# esp32.net
KiCad netlist of a schematic drawn in Altium Designer
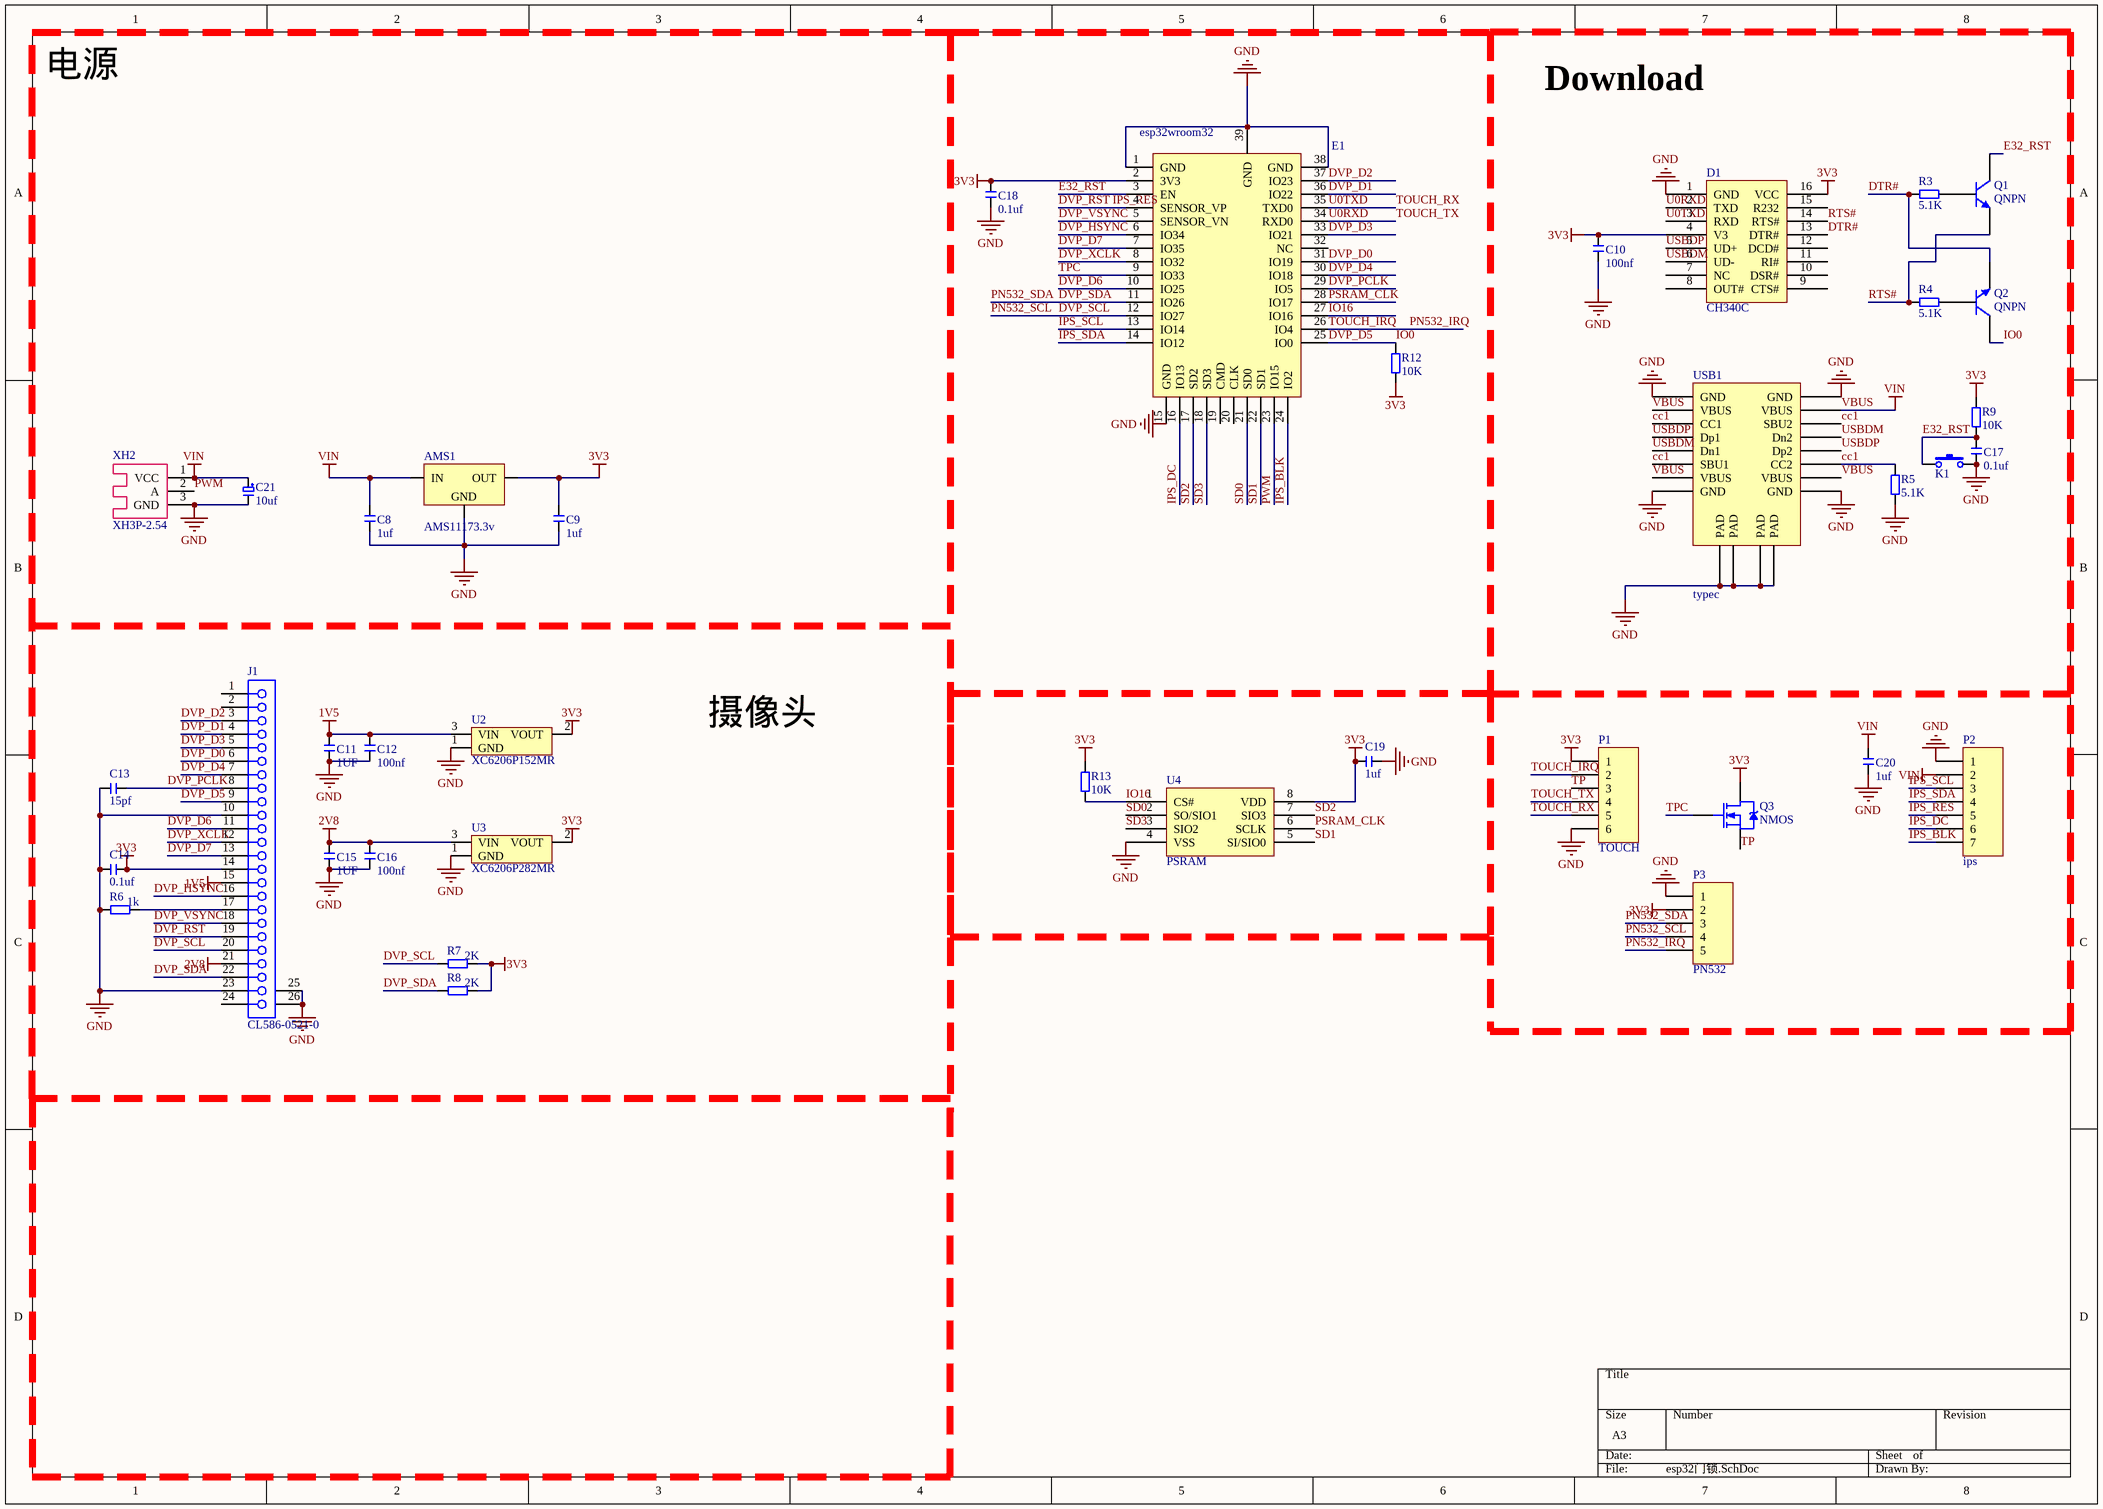
[diagram p0: esp32门锁.SchDoc]

(export (version "E")
  (design (tool "Eeschema 10.0.6"))
  (components
    (comp (ref "AMS1")
      (value "AMS11173.3v")
      (footprint "SOT223")
      (description "Power")
      (libsource (lib "SWJTUCar") (part "AMS1117"))
    )
    (comp (ref "C8")
      (value "1uf")
      (footprint "C0603")
      (description "无极电容")
      (libsource (lib "Robocon_v1.2") (part "CAP"))
    )
    (comp (ref "C9")
      (value "1uf")
      (footprint "C0603")
      (description "无极电容")
      (libsource (lib "Robocon_v1.2") (part "CAP"))
    )
    (comp (ref "C10")
      (value "100nf")
      (footprint "C0603")
      (description "无极电容")
      (libsource (lib "SWJTUCar") (part "CAP"))
    )
    (comp (ref "C11")
      (value "1UF")
      (footprint "C0603")
      (description "无极电容")
      (libsource (lib "SWJTUCar") (part "CAP"))
    )
    (comp (ref "C12")
      (value "100nf")
      (footprint "C0603")
      (description "无极电容")
      (libsource (lib "SWJTUCar") (part "CAP"))
    )
    (comp (ref "C13")
      (value "15pf")
      (footprint "C0603")
      (description "无极电容")
      (libsource (lib "SWJTUCar") (part "CAP"))
    )
    (comp (ref "C14")
      (value "0.1uf")
      (footprint "C0603")
      (description "无极电容")
      (libsource (lib "SWJTUCar") (part "CAP"))
    )
    (comp (ref "C15")
      (value "1UF")
      (footprint "C0603")
      (description "无极电容")
      (libsource (lib "SWJTUCar") (part "CAP"))
    )
    (comp (ref "C16")
      (value "100nf")
      (footprint "C0603")
      (description "无极电容")
      (libsource (lib "SWJTUCar") (part "CAP"))
    )
    (comp (ref "C17")
      (value "0.1uf")
      (footprint "C0603")
      (description "无极电容")
      (libsource (lib "SWJTUCar") (part "CAP"))
    )
    (comp (ref "C18")
      (value "0.1uf")
      (footprint "C0603")
      (description "无极电容")
      (libsource (lib "SWJTUCar") (part "CAP"))
    )
    (comp (ref "C19")
      (value "1uf")
      (footprint "C0603")
      (description "无极电容")
      (libsource (lib "SWJTUCar") (part "CAP"))
    )
    (comp (ref "C20")
      (value "1uf")
      (footprint "C0603")
      (description "无极电容")
      (libsource (lib "SWJTUCar") (part "CAP"))
    )
    (comp (ref "C21")
      (value "10uf")
      (footprint "C4X4")
      (description "电解电容")
      (libsource (lib "SWJTUCar") (part "CAP-Pole_1"))
    )
    (comp (ref "D1") (value "CH340C") (footprint "CH340C") (libsource (lib "LHM_LIB") (part "ch340c")))
    (comp (ref "E1") (value "esp32wroom32") (footprint "esp32U") (libsource (lib "LHM_LIB") (part "esp32")))
    (comp (ref "J1")
      (value "CL586-0521-0")
      (footprint "FH12-24S-0.5SH")
      (description "FH12 Series, \"Flip-Lock\" SMT/ZIF Connector - 0.5mm Spaced Bottom Contact")
      (fields (field (name "PUBLISHER") "Altium Limited"))
      (libsource (lib "HRS FPC-FFC FH12 Series") (part "CL586-0521-0"))
    )
    (comp (ref "K1")
      (value "Key-PB")
      (footprint "KEY-SMD1")
      (description "轻触开关")
      (libsource (lib "SWJTUCar") (part "Key-PB"))
    )
    (comp (ref "P1")
      (value "TOUCH")
      (footprint "HDR1X6")
      (description "Header, 6-Pin")
      (fields (field (name "PUBLISHER") "Altium Limited"))
      (libsource (lib "Miscellaneous Connectors") (part "Header 6"))
    )
    (comp (ref "P2")
      (value "ips")
      (footprint "HDR1X7")
      (description "Header, 7-Pin")
      (fields (field (name "PUBLISHER") "Altium Limited"))
      (libsource (lib "Miscellaneous Connectors") (part "Header 7"))
    )
    (comp (ref "P3")
      (value "PN532")
      (footprint "HDR1X5")
      (description "Header, 5-Pin")
      (fields (field (name "PUBLISHER") "Altium Limited"))
      (libsource (lib "Miscellaneous Connectors") (part "Header 5"))
    )
    (comp (ref "Q1")
      (value "QNPN")
      (footprint "SOT-23B_N")
      (description "NPN Bipolar Transistor")
      (fields (field (name "PUBLISHER") "Altium Limited"))
      (libsource (lib "Miscellaneous Devices") (part "QNPN"))
    )
    (comp (ref "Q2")
      (value "QNPN")
      (footprint "SOT-23B_N")
      (description "NPN Bipolar Transistor")
      (fields (field (name "PUBLISHER") "Altium Limited"))
      (libsource (lib "Miscellaneous Devices") (part "QNPN"))
    )
    (comp (ref "Q3")
      (value "NMOS")
      (footprint "SOT23")
      (description "HEXFET Power MOSFET")
      (fields (field (name "PUBLISHER") "Altium Limited"))
      (libsource (lib "Robocon_v1.2") (part "NOMS"))
    )
    (comp (ref "R3")
      (value "5.1K")
      (footprint "R0603")
      (description "电阻")
      (libsource (lib "SWJTUCar") (part "RES"))
    )
    (comp (ref "R4")
      (value "5.1K")
      (footprint "R0603")
      (description "电阻")
      (libsource (lib "SWJTUCar") (part "RES"))
    )
    (comp (ref "R5")
      (value "5.1K")
      (footprint "R0603")
      (description "电阻")
      (libsource (lib "SWJTUCar") (part "RES"))
    )
    (comp (ref "R6")
      (value "1k")
      (footprint "R0603")
      (description "电阻")
      (libsource (lib "SWJTUCar") (part "RES"))
    )
    (comp (ref "R7")
      (value "2K")
      (footprint "R0603")
      (description "电阻")
      (libsource (lib "SWJTUCar") (part "RES"))
    )
    (comp (ref "R8")
      (value "2K")
      (footprint "R0603")
      (description "电阻")
      (libsource (lib "SWJTUCar") (part "RES"))
    )
    (comp (ref "R9")
      (value "10K")
      (footprint "R0603")
      (description "电阻")
      (libsource (lib "SWJTUCar") (part "RES"))
    )
    (comp (ref "R12")
      (value "10K")
      (footprint "R0603")
      (description "电阻")
      (libsource (lib "SWJTUCar") (part "RES"))
    )
    (comp (ref "R13")
      (value "10K")
      (footprint "R0603")
      (description "电阻")
      (libsource (lib "SWJTUCar") (part "RES"))
    )
    (comp (ref "U2")
      (value "XC6206P152MR")
      (footprint "SOT23-3")
      (description "LDO,SOT23,1.2~5.0V")
      (libsource (lib "Win_Lib") (part "XC6206"))
    )
    (comp (ref "U3")
      (value "XC6206P282MR")
      (footprint "SOT23-3")
      (description "LDO,SOT23,1.2~5.0V")
      (libsource (lib "Win_Lib") (part "XC6206"))
    )
    (comp (ref "U4") (value "PSRAM") (footprint "PSRAM") (libsource (lib "LHM_LIB") (part "PSRAM")))
    (comp (ref "USB1")
      (value "typec")
      (footprint "USB-C-SMD_TYPE-C16PIN")
      (libsource (lib "LHM_LIB") (part "typec16p四脚插板"))
    )
    (comp (ref "XH2")
      (value "XH3P-2.54")
      (footprint "XH2.54-3")
      (description "XH2.54小白头")
      (libsource (lib "SWJTUCar") (part "XH3P-2.54"))
    )
  )
  (nets
    (net (code "1") (name "/DTR#") (class "Default")
      (node (ref "D1") (pin "13") (pinfunction "DTR#_13") (pintype "passive"))
      (node (ref "Q2") (pin "3") (pinfunction "E_3") (pintype "passive"))
      (node (ref "R3") (pin "2") (pinfunction "2_2") (pintype "passive"))
    )
    (net (code "2") (name "/DVP_D0") (class "Default")
      (node (ref "E1") (pin "31") (pinfunction "IO19_31") (pintype "passive"))
      (node (ref "J1") (pin "6") (pinfunction "6_6") (pintype "passive"))
    )
    (net (code "3") (name "/DVP_D1") (class "Default")
      (node (ref "E1") (pin "36") (pinfunction "IO22_36") (pintype "passive"))
      (node (ref "J1") (pin "4") (pinfunction "4_4") (pintype "passive"))
    )
    (net (code "4") (name "/DVP_D2") (class "Default")
      (node (ref "E1") (pin "37") (pinfunction "IO23_37") (pintype "passive"))
      (node (ref "J1") (pin "3") (pinfunction "3_3") (pintype "passive"))
    )
    (net (code "5") (name "/DVP_D3") (class "Default")
      (node (ref "E1") (pin "33") (pinfunction "IO21_33") (pintype "passive"))
      (node (ref "J1") (pin "5") (pinfunction "5_5") (pintype "passive"))
    )
    (net (code "6") (name "/DVP_D4") (class "Default")
      (node (ref "E1") (pin "30") (pinfunction "IO18_30") (pintype "passive"))
      (node (ref "J1") (pin "7") (pinfunction "7_7") (pintype "passive"))
    )
    (net (code "7") (name "/DVP_D5") (class "Default")
      (node (ref "E1") (pin "25") (pinfunction "IO0_25") (pintype "passive"))
      (node (ref "J1") (pin "9") (pinfunction "9_9") (pintype "passive"))
      (node (ref "Q2") (pin "1") (pinfunction "C_1") (pintype "passive"))
      (node (ref "R12") (pin "1") (pinfunction "1_1") (pintype "passive"))
    )
    (net (code "8") (name "/DVP_D6") (class "Default")
      (node (ref "E1") (pin "10") (pinfunction "IO25_10") (pintype "passive"))
      (node (ref "J1") (pin "11") (pinfunction "11_11") (pintype "passive"))
    )
    (net (code "9") (name "/DVP_D7") (class "Default")
      (node (ref "E1") (pin "7") (pinfunction "IO35_7") (pintype "passive"))
      (node (ref "J1") (pin "13") (pinfunction "13_13") (pintype "passive"))
    )
    (net (code "10") (name "/DVP_HSYNC") (class "Default")
      (node (ref "E1") (pin "6") (pinfunction "IO34_6") (pintype "passive"))
      (node (ref "J1") (pin "16") (pinfunction "16_16") (pintype "passive"))
    )
    (net (code "11") (name "/DVP_PCLK") (class "Default")
      (node (ref "C13") (pin "1") (pinfunction "1_1") (pintype "passive"))
      (node (ref "E1") (pin "29") (pinfunction "IO5_29") (pintype "passive"))
      (node (ref "J1") (pin "8") (pinfunction "8_8") (pintype "passive"))
    )
    (net (code "12") (name "/DVP_RST") (class "Default")
      (node (ref "E1") (pin "4") (pinfunction "SENSOR_VP_4") (pintype "passive"))
      (node (ref "J1") (pin "19") (pinfunction "19_19") (pintype "passive"))
      (node (ref "P2") (pin "5") (pinfunction "5_5") (pintype "passive"))
    )
    (net (code "13") (name "/DVP_SCL") (class "Default")
      (node (ref "E1") (pin "12") (pinfunction "IO27_12") (pintype "passive"))
      (node (ref "J1") (pin "20") (pinfunction "20_20") (pintype "passive"))
      (node (ref "P3") (pin "4") (pinfunction "4_4") (pintype "passive"))
      (node (ref "R7") (pin "2") (pinfunction "2_2") (pintype "passive"))
    )
    (net (code "14") (name "/DVP_SDA") (class "Default")
      (node (ref "E1") (pin "11") (pinfunction "IO26_11") (pintype "passive"))
      (node (ref "J1") (pin "22") (pinfunction "22_22") (pintype "passive"))
      (node (ref "P3") (pin "3") (pinfunction "3_3") (pintype "passive"))
      (node (ref "R8") (pin "2") (pinfunction "2_2") (pintype "passive"))
    )
    (net (code "15") (name "/DVP_VSYNC") (class "Default")
      (node (ref "E1") (pin "5") (pinfunction "SENSOR_VN_5") (pintype "passive"))
      (node (ref "J1") (pin "18") (pinfunction "18_18") (pintype "passive"))
    )
    (net (code "16") (name "/DVP_XCLK") (class "Default")
      (node (ref "E1") (pin "8") (pinfunction "IO32_8") (pintype "passive"))
      (node (ref "J1") (pin "12") (pinfunction "12_12") (pintype "passive"))
    )
    (net (code "17") (name "/E32_RST") (class "Default")
      (node (ref "C17") (pin "2") (pinfunction "2_2") (pintype "passive"))
      (node (ref "E1") (pin "3") (pinfunction "EN_3") (pintype "passive"))
      (node (ref "K1") (pin "1") (pinfunction "1_1") (pintype "passive"))
      (node (ref "Q1") (pin "1") (pinfunction "C_1") (pintype "passive"))
      (node (ref "R9") (pin "1") (pinfunction "1_1") (pintype "passive"))
    )
    (net (code "18") (name "/IO16") (class "Default")
      (node (ref "E1") (pin "27") (pinfunction "IO16_27") (pintype "passive"))
      (node (ref "R13") (pin "2") (pinfunction "2_2") (pintype "passive"))
      (node (ref "U4") (pin "1") (pinfunction "CS#_1") (pintype "passive"))
    )
    (net (code "19") (name "/IPS_BLK") (class "Default")
      (node (ref "E1") (pin "24") (pinfunction "IO2_24") (pintype "passive"))
      (node (ref "P2") (pin "7") (pinfunction "7_7") (pintype "passive"))
    )
    (net (code "20") (name "/IPS_DC") (class "Default")
      (node (ref "E1") (pin "16") (pinfunction "IO13_16") (pintype "passive"))
      (node (ref "P2") (pin "6") (pinfunction "6_6") (pintype "passive"))
    )
    (net (code "21") (name "/IPS_SCL") (class "Default")
      (node (ref "E1") (pin "13") (pinfunction "IO14_13") (pintype "passive"))
      (node (ref "P2") (pin "3") (pinfunction "3_3") (pintype "passive"))
    )
    (net (code "22") (name "/IPS_SDA") (class "Default")
      (node (ref "E1") (pin "14") (pinfunction "IO12_14") (pintype "passive"))
      (node (ref "P2") (pin "4") (pinfunction "4_4") (pintype "passive"))
    )
    (net (code "23") (name "/PN532_IRQ") (class "Default")
      (node (ref "E1") (pin "26") (pinfunction "IO4_26") (pintype "passive"))
      (node (ref "P1") (pin "2") (pinfunction "2_2") (pintype "passive"))
      (node (ref "P3") (pin "5") (pinfunction "5_5") (pintype "passive"))
    )
    (net (code "24") (name "/PSRAM_CLK") (class "Default")
      (node (ref "E1") (pin "28") (pinfunction "IO17_28") (pintype "passive"))
      (node (ref "U4") (pin "6") (pinfunction "SCLK_6") (pintype "passive"))
    )
    (net (code "25") (name "/PWM") (class "Default")
      (node (ref "E1") (pin "23") (pinfunction "IO15_23") (pintype "passive"))
      (node (ref "XH2") (pin "2") (pinfunction "A_2") (pintype "passive"))
    )
    (net (code "26") (name "/RTS#") (class "Default")
      (node (ref "D1") (pin "14") (pinfunction "RTS#_14") (pintype "passive"))
      (node (ref "Q1") (pin "3") (pinfunction "E_3") (pintype "passive"))
      (node (ref "R4") (pin "2") (pinfunction "2_2") (pintype "passive"))
    )
    (net (code "27") (name "/SD0") (class "Default")
      (node (ref "E1") (pin "21") (pinfunction "SD0_21") (pintype "passive"))
      (node (ref "U4") (pin "2") (pinfunction "SO/SIO1_2") (pintype "passive"))
    )
    (net (code "28") (name "/SD1") (class "Default")
      (node (ref "E1") (pin "22") (pinfunction "SD1_22") (pintype "passive"))
      (node (ref "U4") (pin "5") (pinfunction "SI/SIO0_5") (pintype "passive"))
    )
    (net (code "29") (name "/SD2") (class "Default")
      (node (ref "E1") (pin "17") (pinfunction "SD2_17") (pintype "passive"))
      (node (ref "U4") (pin "7") (pinfunction "SIO3_7") (pintype "passive"))
    )
    (net (code "30") (name "/SD3") (class "Default")
      (node (ref "E1") (pin "18") (pinfunction "SD3_18") (pintype "passive"))
      (node (ref "U4") (pin "3") (pinfunction "SIO2_3") (pintype "passive"))
    )
    (net (code "31") (name "/TOUCH_RX") (class "Default")
      (node (ref "D1") (pin "3") (pinfunction "RXD_3") (pintype "passive"))
      (node (ref "E1") (pin "35") (pinfunction "TXD0_35") (pintype "passive"))
      (node (ref "P1") (pin "5") (pinfunction "5_5") (pintype "passive"))
    )
    (net (code "32") (name "/TOUCH_TX") (class "Default")
      (node (ref "D1") (pin "2") (pinfunction "TXD_2") (pintype "passive"))
      (node (ref "E1") (pin "34") (pinfunction "RXD0_34") (pintype "passive"))
      (node (ref "P1") (pin "4") (pinfunction "4_4") (pintype "passive"))
    )
    (net (code "33") (name "/TP") (class "Default")
      (node (ref "P1") (pin "3") (pinfunction "3_3") (pintype "passive"))
      (node (ref "Q3") (pin "3") (pinfunction "S_3") (pintype "passive"))
    )
    (net (code "34") (name "/TPC") (class "Default")
      (node (ref "E1") (pin "9") (pinfunction "IO33_9") (pintype "passive"))
      (node (ref "Q3") (pin "1") (pinfunction "15_1") (pintype "passive"))
    )
    (net (code "35") (name "/USBDM") (class "Default")
      (node (ref "D1") (pin "6") (pinfunction "UD-_6") (pintype "passive"))
      (node (ref "USB1") (pin "A7") (pinfunction "Dn1_A7") (pintype "passive"))
      (node (ref "USB1") (pin "B7") (pinfunction "Dn2_B7") (pintype "passive"))
    )
    (net (code "36") (name "/USBDP") (class "Default")
      (node (ref "D1") (pin "5") (pinfunction "UD+_5") (pintype "passive"))
      (node (ref "USB1") (pin "A6") (pinfunction "Dp1_A6") (pintype "passive"))
      (node (ref "USB1") (pin "B6") (pinfunction "Dp2_B6") (pintype "passive"))
    )
    (net (code "37") (name "/cc1") (class "Default")
      (node (ref "R5") (pin "2") (pinfunction "2_2") (pintype "passive"))
      (node (ref "USB1") (pin "A5") (pinfunction "CC1_A5") (pintype "passive"))
      (node (ref "USB1") (pin "A8") (pinfunction "SBU1_A8") (pintype "passive"))
      (node (ref "USB1") (pin "B5") (pinfunction "CC2_B5") (pintype "passive"))
      (node (ref "USB1") (pin "B8") (pinfunction "SBU2_B8") (pintype "passive"))
    )
    (net (code "38") (name "1V5") (class "Default")
      (node (ref "C11") (pin "2") (pinfunction "2_2") (pintype "passive"))
      (node (ref "C12") (pin "2") (pinfunction "2_2") (pintype "passive"))
      (node (ref "J1") (pin "15") (pinfunction "15_15") (pintype "passive"))
      (node (ref "U2") (pin "3") (pinfunction "VIN_3") (pintype "passive"))
    )
    (net (code "39") (name "2V8") (class "Default")
      (node (ref "C15") (pin "2") (pinfunction "2_2") (pintype "passive"))
      (node (ref "C16") (pin "2") (pinfunction "2_2") (pintype "passive"))
      (node (ref "J1") (pin "21") (pinfunction "21_21") (pintype "passive"))
      (node (ref "U3") (pin "3") (pinfunction "VIN_3") (pintype "passive"))
    )
    (net (code "40") (name "3V3") (class "Default")
      (node (ref "AMS1") (pin "2") (pinfunction "OUT_2") (pintype "power_in"))
      (node (ref "C10") (pin "2") (pinfunction "2_2") (pintype "passive"))
      (node (ref "C14") (pin "1") (pinfunction "1_1") (pintype "passive"))
      (node (ref "C18") (pin "2") (pinfunction "2_2") (pintype "passive"))
      (node (ref "C19") (pin "2") (pinfunction "2_2") (pintype "passive"))
      (node (ref "C9") (pin "2") (pinfunction "2_2") (pintype "passive"))
      (node (ref "D1") (pin "16") (pinfunction "VCC_16") (pintype "passive"))
      (node (ref "D1") (pin "4") (pinfunction "V3_4") (pintype "passive"))
      (node (ref "E1") (pin "2") (pinfunction "3V3_2") (pintype "passive"))
      (node (ref "J1") (pin "14") (pinfunction "14_14") (pintype "passive"))
      (node (ref "P1") (pin "1") (pinfunction "1_1") (pintype "passive"))
      (node (ref "P3") (pin "2") (pinfunction "2_2") (pintype "passive"))
      (node (ref "Q3") (pin "2") (pinfunction "D_2") (pintype "passive"))
      (node (ref "R12") (pin "2") (pinfunction "2_2") (pintype "passive"))
      (node (ref "R13") (pin "1") (pinfunction "1_1") (pintype "passive"))
      (node (ref "R7") (pin "1") (pinfunction "1_1") (pintype "passive"))
      (node (ref "R8") (pin "1") (pinfunction "1_1") (pintype "passive"))
      (node (ref "R9") (pin "2") (pinfunction "2_2") (pintype "passive"))
      (node (ref "U2") (pin "2") (pinfunction "VOUT_2") (pintype "passive"))
      (node (ref "U3") (pin "2") (pinfunction "VOUT_2") (pintype "passive"))
      (node (ref "U4") (pin "8") (pinfunction "VDD_8") (pintype "passive"))
    )
    (net (code "41") (name "GND") (class "Default")
      (node (ref "AMS1") (pin "1") (pinfunction "GND_1") (pintype "power_in"))
      (node (ref "C10") (pin "1") (pinfunction "1_1") (pintype "passive"))
      (node (ref "C11") (pin "1") (pinfunction "1_1") (pintype "passive"))
      (node (ref "C12") (pin "1") (pinfunction "1_1") (pintype "passive"))
      (node (ref "C13") (pin "2") (pinfunction "2_2") (pintype "passive"))
      (node (ref "C14") (pin "2") (pinfunction "2_2") (pintype "passive"))
      (node (ref "C15") (pin "1") (pinfunction "1_1") (pintype "passive"))
      (node (ref "C16") (pin "1") (pinfunction "1_1") (pintype "passive"))
      (node (ref "C17") (pin "1") (pinfunction "1_1") (pintype "passive"))
      (node (ref "C18") (pin "1") (pinfunction "1_1") (pintype "passive"))
      (node (ref "C19") (pin "1") (pinfunction "1_1") (pintype "passive"))
      (node (ref "C20") (pin "2") (pinfunction "2_2") (pintype "passive"))
      (node (ref "C21") (pin "2") (pinfunction "2_2") (pintype "passive"))
      (node (ref "C8") (pin "1") (pinfunction "1_1") (pintype "passive"))
      (node (ref "C9") (pin "1") (pinfunction "1_1") (pintype "passive"))
      (node (ref "D1") (pin "1") (pinfunction "GND_1") (pintype "passive"))
      (node (ref "E1") (pin "1") (pinfunction "GND_1") (pintype "passive"))
      (node (ref "E1") (pin "15") (pinfunction "GND_15") (pintype "passive"))
      (node (ref "E1") (pin "38") (pinfunction "GND_38") (pintype "passive"))
      (node (ref "E1") (pin "39") (pinfunction "GND_39") (pintype "passive"))
      (node (ref "J1") (pin "10") (pinfunction "10_10") (pintype "passive"))
      (node (ref "J1") (pin "23") (pinfunction "23_23") (pintype "passive"))
      (node (ref "J1") (pin "25") (pinfunction "MH1_25") (pintype "passive"))
      (node (ref "J1") (pin "26") (pinfunction "MH2_26") (pintype "passive"))
      (node (ref "K1") (pin "2") (pinfunction "2_2") (pintype "passive"))
      (node (ref "P1") (pin "6") (pinfunction "6_6") (pintype "passive"))
      (node (ref "P2") (pin "1") (pinfunction "1_1") (pintype "passive"))
      (node (ref "P3") (pin "1") (pinfunction "1_1") (pintype "passive"))
      (node (ref "R5") (pin "1") (pinfunction "1_1") (pintype "passive"))
      (node (ref "R6") (pin "2") (pinfunction "2_2") (pintype "passive"))
      (node (ref "U2") (pin "1") (pinfunction "GND_1") (pintype "passive"))
      (node (ref "U3") (pin "1") (pinfunction "GND_1") (pintype "passive"))
      (node (ref "U4") (pin "4") (pinfunction "VSS_4") (pintype "passive"))
      (node (ref "USB1") (pin "A1B12") (pinfunction "GND_A1B12") (pintype "passive"))
      (node (ref "USB1") (pin "B1A12") (pinfunction "GND_B1A12") (pintype "passive"))
      (node (ref "USB1") (pin "S") (pinfunction "PAD_S") (pintype "passive"))
      (node (ref "XH2") (pin "3") (pinfunction "GND_3") (pintype "passive"))
    )
    (net (code "42") (name "Net-(J1-Pad17)") (class "Default")
      (node (ref "J1") (pin "17") (pinfunction "17_17") (pintype "passive"))
      (node (ref "R6") (pin "1") (pinfunction "1_1") (pintype "passive"))
    )
    (net (code "43") (name "Net-(Q1-B)") (class "Default")
      (node (ref "Q1") (pin "2") (pinfunction "B_2") (pintype "passive"))
      (node (ref "R3") (pin "1") (pinfunction "1_1") (pintype "passive"))
    )
    (net (code "44") (name "Net-(Q2-B)") (class "Default")
      (node (ref "Q2") (pin "2") (pinfunction "B_2") (pintype "passive"))
      (node (ref "R4") (pin "1") (pinfunction "1_1") (pintype "passive"))
    )
    (net (code "45") (name "VIN") (class "Default")
      (node (ref "AMS1") (pin "3") (pinfunction "IN_3") (pintype "power_in"))
      (node (ref "C20") (pin "1") (pinfunction "1_1") (pintype "passive"))
      (node (ref "C21") (pin "1") (pinfunction "1_1") (pintype "passive"))
      (node (ref "C8") (pin "2") (pinfunction "2_2") (pintype "passive"))
      (node (ref "P2") (pin "2") (pinfunction "2_2") (pintype "passive"))
      (node (ref "USB1") (pin "A4B9") (pinfunction "VBUS_A4B9") (pintype "passive"))
      (node (ref "USB1") (pin "B4A9") (pinfunction "VBUS_B4A9") (pintype "passive"))
      (node (ref "XH2") (pin "1") (pinfunction "VCC_1") (pintype "passive"))
    )
    (net (code "46") (name "unconnected-(D1-CTS#-Pad9)") (class "Default")
      (node (ref "D1") (pin "9") (pinfunction "CTS#_9") (pintype "passive"))
    )
    (net (code "47") (name "unconnected-(D1-DCD#-Pad12)") (class "Default")
      (node (ref "D1") (pin "12") (pinfunction "DCD#_12") (pintype "passive"))
    )
    (net (code "48") (name "unconnected-(D1-DSR#-Pad10)") (class "Default")
      (node (ref "D1") (pin "10") (pinfunction "DSR#_10") (pintype "passive"))
    )
    (net (code "49") (name "unconnected-(D1-NC-Pad7)") (class "Default")
      (node (ref "D1") (pin "7") (pinfunction "NC_7") (pintype "passive"))
    )
    (net (code "50") (name "unconnected-(D1-OUT#-Pad8)") (class "Default")
      (node (ref "D1") (pin "8") (pinfunction "OUT#_8") (pintype "passive"))
    )
    (net (code "51") (name "unconnected-(D1-R232-Pad15)") (class "Default")
      (node (ref "D1") (pin "15") (pinfunction "R232_15") (pintype "passive"))
    )
    (net (code "52") (name "unconnected-(D1-RI#-Pad11)") (class "Default")
      (node (ref "D1") (pin "11") (pinfunction "RI#_11") (pintype "passive"))
    )
    (net (code "53") (name "unconnected-(E1-CLK-Pad20)") (class "Default")
      (node (ref "E1") (pin "20") (pinfunction "CLK_20") (pintype "passive"))
    )
    (net (code "54") (name "unconnected-(E1-CMD-Pad19)") (class "Default")
      (node (ref "E1") (pin "19") (pinfunction "CMD_19") (pintype "passive"))
    )
    (net (code "55") (name "unconnected-(E1-NC-Pad32)") (class "Default")
      (node (ref "E1") (pin "32") (pinfunction "NC_32") (pintype "passive"))
    )
    (net (code "56") (name "unconnected-(J1-Pad1)") (class "Default")
      (node (ref "J1") (pin "1") (pinfunction "1_1") (pintype "passive"))
    )
    (net (code "57") (name "unconnected-(J1-Pad2)") (class "Default")
      (node (ref "J1") (pin "2") (pinfunction "2_2") (pintype "passive"))
    )
    (net (code "58") (name "unconnected-(J1-Pad24)") (class "Default")
      (node (ref "J1") (pin "24") (pinfunction "24_24") (pintype "passive"))
    )
  )
)
